# SensorTile_Breakout.net
KiCad netlist of a schematic drawn in EAGLE
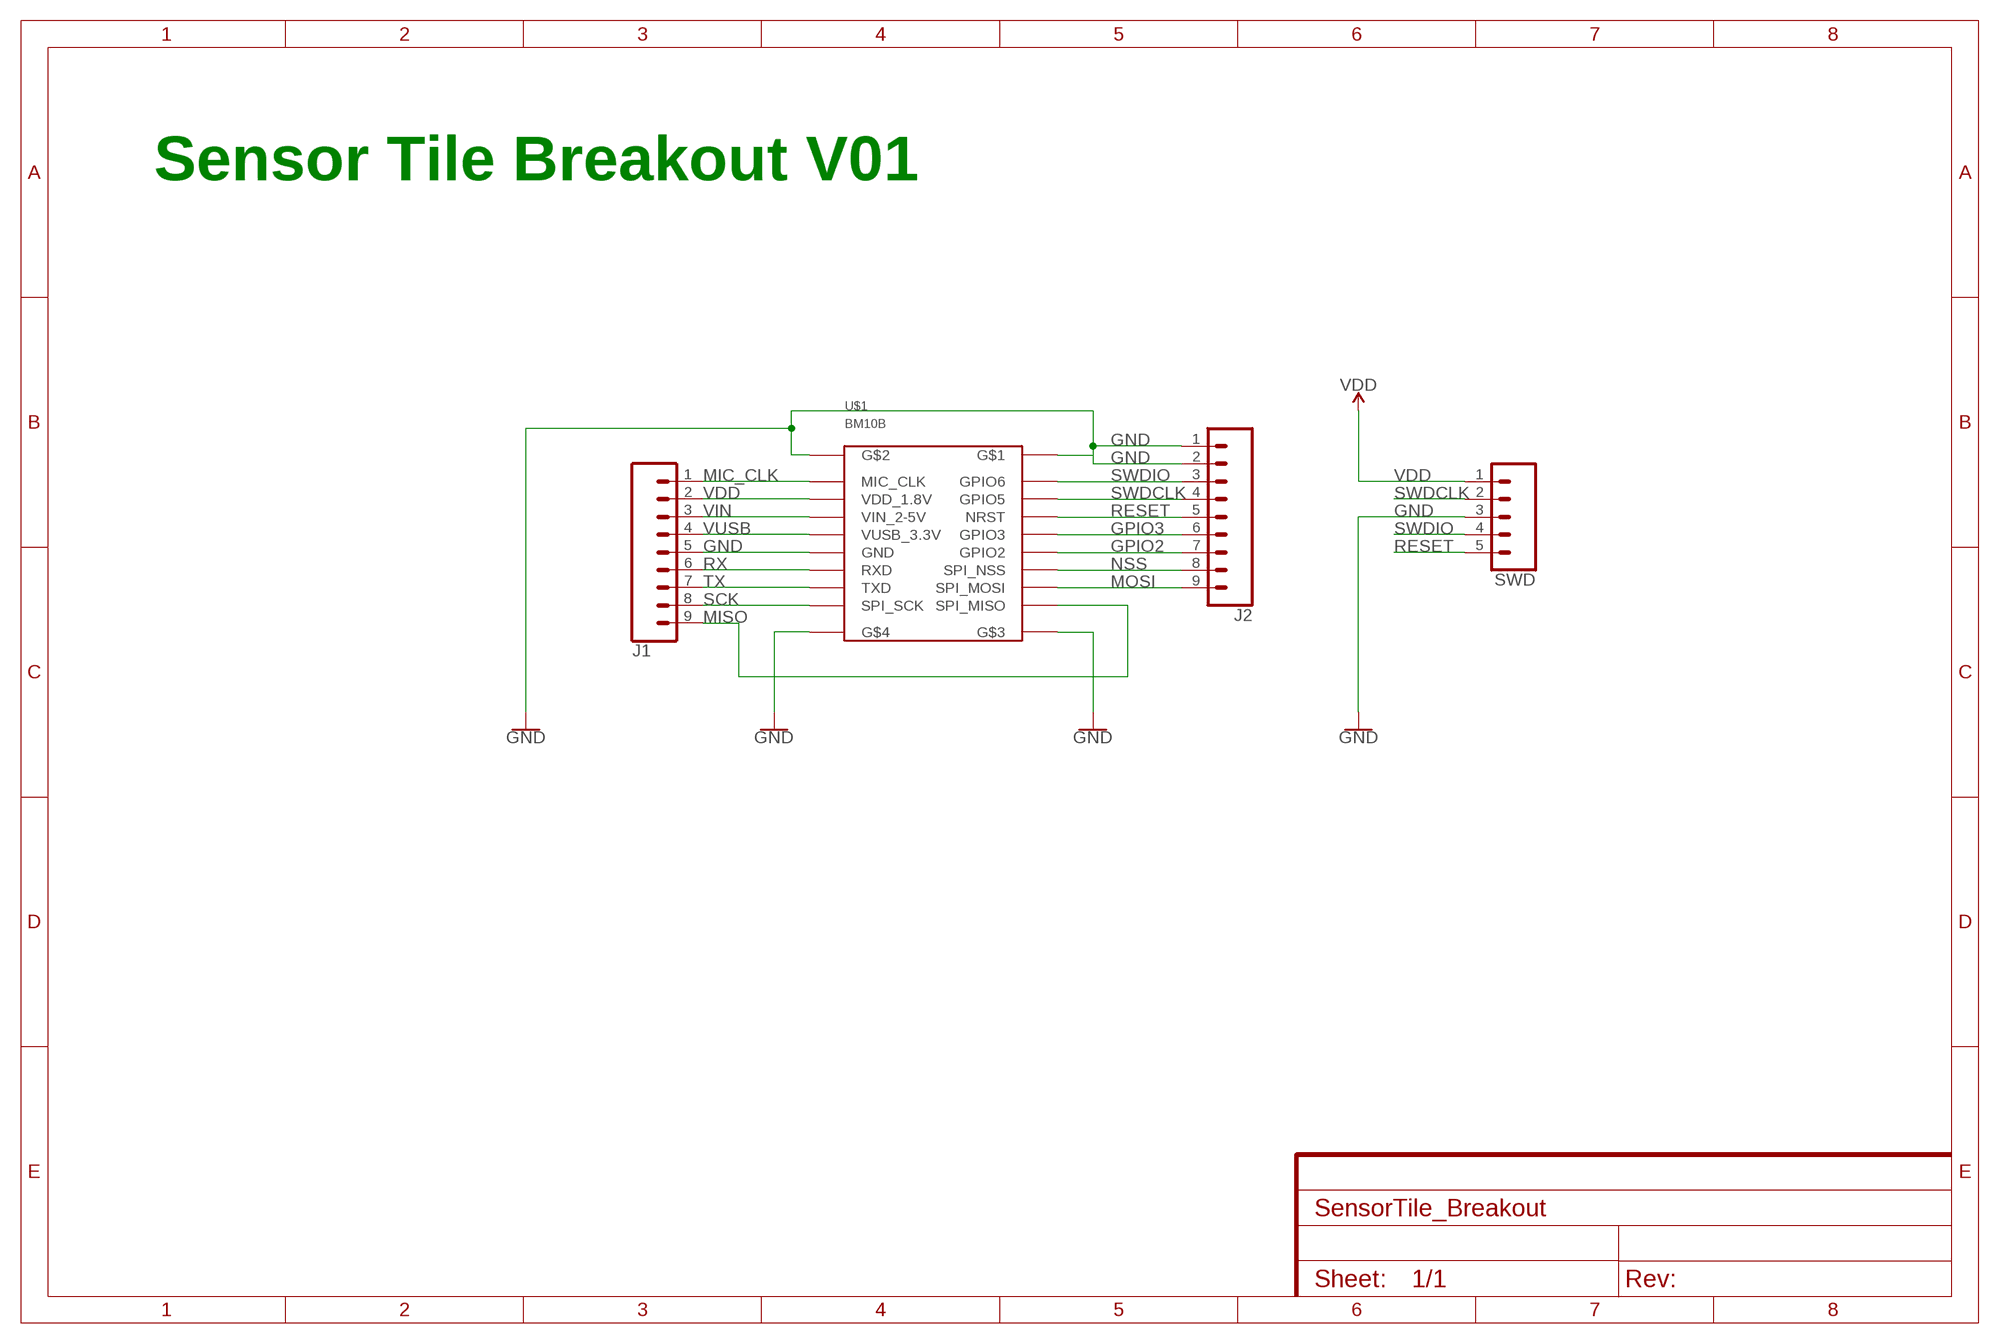
[diagram p0: schematic, sheet 1]

(export (version "E")
  (design (tool "Eeschema 10.0.6"))
  (components
    (comp (ref "J1")
      (value "CONN_09")
      (footprint "eagle-import:1X09")
      (libsource (lib "eagle-import") (part "CONN_09"))
    )
    (comp (ref "J2")
      (value "CONN_09")
      (footprint "eagle-import:1X09")
      (libsource (lib "eagle-import") (part "CONN_09"))
    )
    (comp (ref "SWD")
      (value "CONN_05")
      (footprint "eagle-import:1X05")
      (libsource (lib "eagle-import") (part "CONN_05"))
    )
    (comp (ref "U$1")
      (value "BM10B")
      (footprint "eagle-import:BM10B(0.8)-16DP-0.4V(51)")
      (libsource (lib "eagle-import") (part "BM10B(0.8)-16DP-0.4V(51)"))
    )
  )
  (nets
    (net (code "1") (name "/GPIO2") (class "Default")
      (node (ref "J2") (pin "7") (pinfunction "7_7") (pintype "passive"))
      (node (ref "U$1") (pin "GPIO2") (pinfunction "GPIO2_GPIO2") (pintype "bidirectional"))
    )
    (net (code "2") (name "/GPIO3") (class "Default")
      (node (ref "J2") (pin "6") (pinfunction "6_6") (pintype "passive"))
      (node (ref "U$1") (pin "GPIO3") (pinfunction "GPIO3_GPIO3") (pintype "bidirectional"))
    )
    (net (code "3") (name "/MIC_CLK") (class "Default")
      (node (ref "J1") (pin "1") (pinfunction "1_1") (pintype "passive"))
      (node (ref "U$1") (pin "MIC_CLK") (pinfunction "MIC_CLK_MIC_CLK") (pintype "bidirectional"))
    )
    (net (code "4") (name "/MISO") (class "Default")
      (node (ref "J1") (pin "9") (pinfunction "9_9") (pintype "passive"))
      (node (ref "U$1") (pin "SPI_MISO") (pinfunction "SPI_MISO_SPI_MISO") (pintype "bidirectional"))
    )
    (net (code "5") (name "/MOSI") (class "Default")
      (node (ref "J2") (pin "9") (pinfunction "9_9") (pintype "passive"))
      (node (ref "U$1") (pin "SPI_MOSI") (pinfunction "SPI_MOSI_SPI_MOSI") (pintype "bidirectional"))
    )
    (net (code "6") (name "/NSS") (class "Default")
      (node (ref "J2") (pin "8") (pinfunction "8_8") (pintype "passive"))
      (node (ref "U$1") (pin "SPI_NSS") (pinfunction "SPI_NSS_SPI_NSS") (pintype "bidirectional"))
    )
    (net (code "7") (name "/RESET") (class "Default")
      (node (ref "J2") (pin "5") (pinfunction "5_5") (pintype "passive"))
      (node (ref "SWD") (pin "5") (pinfunction "5_5") (pintype "passive"))
      (node (ref "U$1") (pin "NRST") (pinfunction "NRST_NRST") (pintype "bidirectional"))
    )
    (net (code "8") (name "/RX") (class "Default")
      (node (ref "J1") (pin "6") (pinfunction "6_6") (pintype "passive"))
      (node (ref "U$1") (pin "RXD") (pinfunction "RXD_RXD") (pintype "bidirectional"))
    )
    (net (code "9") (name "/SCK") (class "Default")
      (node (ref "J1") (pin "8") (pinfunction "8_8") (pintype "passive"))
      (node (ref "U$1") (pin "SPI_SCK") (pinfunction "SPI_SCK_SPI_SCK") (pintype "bidirectional"))
    )
    (net (code "10") (name "/SWDCLK") (class "Default")
      (node (ref "J2") (pin "4") (pinfunction "4_4") (pintype "passive"))
      (node (ref "SWD") (pin "2") (pinfunction "2_2") (pintype "passive"))
      (node (ref "U$1") (pin "GPIO5") (pinfunction "GPIO5_GPIO5") (pintype "bidirectional"))
    )
    (net (code "11") (name "/SWDIO") (class "Default")
      (node (ref "J2") (pin "3") (pinfunction "3_3") (pintype "passive"))
      (node (ref "SWD") (pin "4") (pinfunction "4_4") (pintype "passive"))
      (node (ref "U$1") (pin "GPIO6") (pinfunction "GPIO6_GPIO6") (pintype "bidirectional"))
    )
    (net (code "12") (name "/TX") (class "Default")
      (node (ref "J1") (pin "7") (pinfunction "7_7") (pintype "passive"))
      (node (ref "U$1") (pin "TXD") (pinfunction "TXD_TXD") (pintype "bidirectional"))
    )
    (net (code "13") (name "/VIN") (class "Default")
      (node (ref "J1") (pin "3") (pinfunction "3_3") (pintype "passive"))
      (node (ref "U$1") (pin "VIN_2-5V") (pinfunction "VIN_2-5V_VIN_2-5V") (pintype "bidirectional"))
    )
    (net (code "14") (name "/VUSB") (class "Default")
      (node (ref "J1") (pin "4") (pinfunction "4_4") (pintype "passive"))
      (node (ref "U$1") (pin "VUSB_3.3V") (pinfunction "VUSB_3.3V_VUSB_3.3V") (pintype "bidirectional"))
    )
    (net (code "15") (name "GND") (class "Default")
      (node (ref "J1") (pin "5") (pinfunction "5_5") (pintype "passive"))
      (node (ref "J2") (pin "1") (pinfunction "1_1") (pintype "passive"))
      (node (ref "J2") (pin "2") (pinfunction "2_2") (pintype "passive"))
      (node (ref "SWD") (pin "3") (pinfunction "3_3") (pintype "passive"))
      (node (ref "U$1") (pin "G$1") (pinfunction "G$1_G$1") (pintype "bidirectional"))
      (node (ref "U$1") (pin "G$2") (pinfunction "G$2_G$2") (pintype "bidirectional"))
      (node (ref "U$1") (pin "G$3") (pinfunction "G$3_G$3") (pintype "bidirectional"))
      (node (ref "U$1") (pin "G$4") (pinfunction "G$4_G$4") (pintype "bidirectional"))
      (node (ref "U$1") (pin "GND$1") (pinfunction "GND_GND$1") (pintype "bidirectional"))
    )
    (net (code "16") (name "VDD") (class "Default")
      (node (ref "J1") (pin "2") (pinfunction "2_2") (pintype "passive"))
      (node (ref "SWD") (pin "1") (pinfunction "1_1") (pintype "passive"))
      (node (ref "U$1") (pin "VDD_1.8V") (pinfunction "VDD_1.8V_VDD_1.8V") (pintype "bidirectional"))
    )
  )
)
